# sch.net
KiCad netlist of a schematic drawn in EAGLE
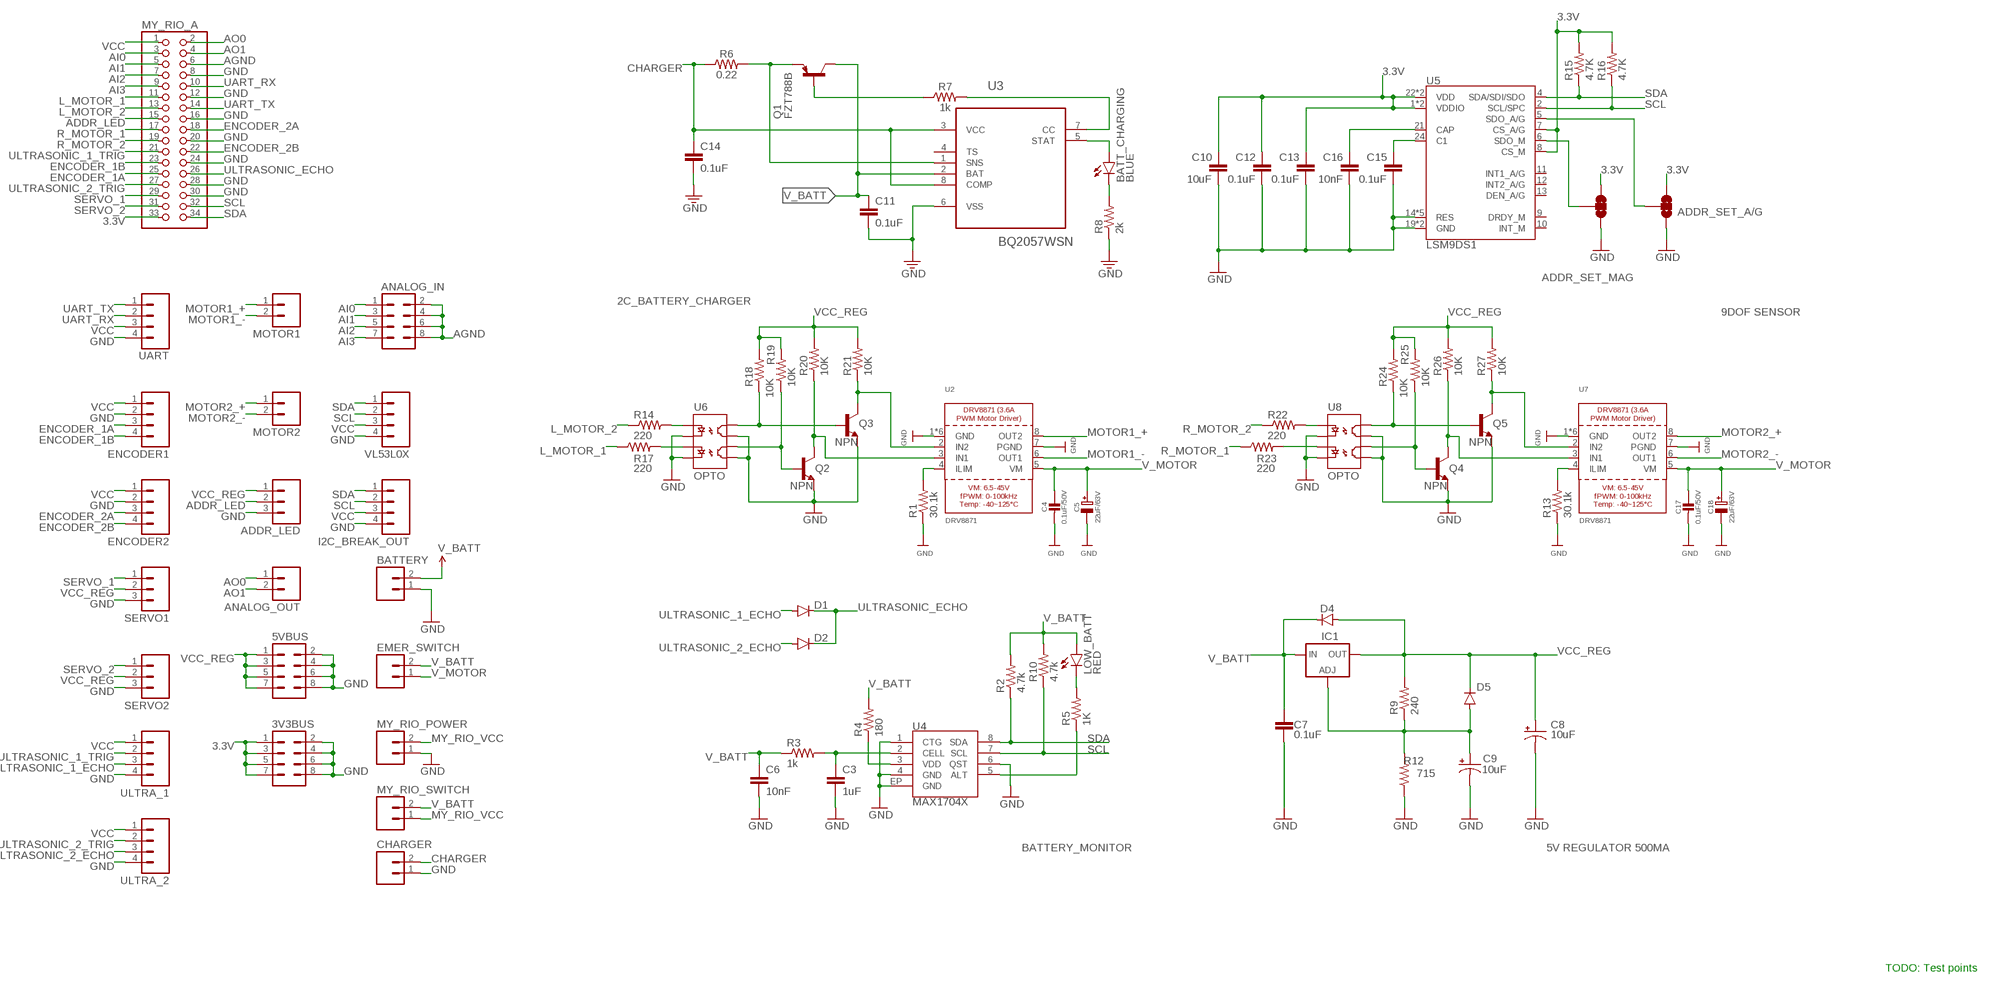
[diagram p0: schematic, sheet 1]

(export (version "E")
  (design (tool "Eeschema 10.0.6"))
  (components
    (comp (ref "3V3BUS")
      (value "M04X2")
      (footprint "eagle-import:2X4")
      (libsource (lib "eagle-import") (part "M04X2"))
    )
    (comp (ref "5VBUS")
      (value "M04X2")
      (footprint "eagle-import:2X4")
      (libsource (lib "eagle-import") (part "M04X2"))
    )
    (comp (ref "ADDR_LED")
      (value "M03POLAR")
      (footprint "eagle-import:MOLEX-1X3")
      (libsource (lib "eagle-import") (part "M03POLAR"))
    )
    (comp (ref "ADDR_SET_A/G")
      (value "JUMPER-PAD-3-2OF3_NC_BY_TRACE_SMALL")
      (footprint "eagle-import:PAD-JUMPER-3-2OF3_NC_BY_TRACE_YES_SILK_FULL_BOX")
      (libsource (lib "eagle-import") (part "JUMPER-PAD-3-2OF3_NC_BY_TRACE_SMALL"))
    )
    (comp (ref "ADDR_SET_MAG")
      (value "JUMPER-PAD-3-2OF3_NC_BY_TRACE_SMALL")
      (footprint "eagle-import:PAD-JUMPER-3-2OF3_NC_BY_TRACE_YES_SILK_FULL_BOX")
      (libsource (lib "eagle-import") (part "JUMPER-PAD-3-2OF3_NC_BY_TRACE_SMALL"))
    )
    (comp (ref "ANALOG_IN")
      (value "M04X2")
      (footprint "eagle-import:2X4")
      (libsource (lib "eagle-import") (part "M04X2"))
    )
    (comp (ref "ANALOG_OUT")
      (value "M021X02_NO_SILK")
      (footprint "eagle-import:1X02_NO_SILK@1")
      (libsource (lib "eagle-import") (part "M021X02_NO_SILK"))
    )
    (comp (ref "BATTERY")
      (value "CONN_02")
      (footprint "eagle-import:1X02")
      (libsource (lib "eagle-import") (part "CONN_02"))
    )
    (comp (ref "BATT_CHARGING")
      (value "BLUE")
      (footprint "eagle-import:LED-0603")
      (libsource (lib "eagle-import") (part "LED-BLUE0603"))
    )
    (comp (ref "C3")
      (value "1uF")
      (footprint "eagle-import:0402-CAP")
      (libsource (lib "eagle-import") (part "CAP0402-CAP"))
    )
    (comp (ref "C4")
      (value "0.1uF/50V")
      (footprint "eagle-import:0805-NO")
      (libsource (lib "eagle-import") (part "CAP_CERAMIC0805-NOOUTLINE"))
    )
    (comp (ref "C5")
      (value "22uF/63V")
      (footprint "eagle-import:PANASONIC_D")
      (libsource (lib "eagle-import") (part "CAP_ELECTROLYTICPANASONIC_D"))
    )
    (comp (ref "C6")
      (value "10nF")
      (footprint "eagle-import:0402-CAP")
      (libsource (lib "eagle-import") (part "CAP0402-CAP"))
    )
    (comp (ref "C7")
      (value "0.1uF")
      (footprint "eagle-import:0603-CAP")
      (libsource (lib "eagle-import") (part "0.1UF-25V(+80/-20%)(0603)"))
    )
    (comp (ref "C8")
      (value "10uF")
      (footprint "eagle-import:EIA3216")
      (libsource (lib "eagle-import") (part "10UF-16V-10%(TANT)"))
    )
    (comp (ref "C9")
      (value "10uF")
      (footprint "eagle-import:EIA3216")
      (libsource (lib "eagle-import") (part "10UF-16V-10%(TANT)"))
    )
    (comp (ref "C10")
      (value "10uF")
      (footprint "eagle-import:0603-CAP")
      (libsource (lib "eagle-import") (part "10UF-6.3V-20%(0603)"))
    )
    (comp (ref "C11")
      (value "0.1uF")
      (footprint "eagle-import:0603")
      (libsource (lib "eagle-import") (part "0.1UF-0603-25V-(+80/-20%)"))
    )
    (comp (ref "C12")
      (value "0.1uF")
      (footprint "eagle-import:0603-CAP")
      (libsource (lib "eagle-import") (part "0.1UF-25V(+80/-20%)(0603)"))
    )
    (comp (ref "C13")
      (value "0.1uF")
      (footprint "eagle-import:0603-CAP")
      (libsource (lib "eagle-import") (part "0.1UF-25V(+80/-20%)(0603)"))
    )
    (comp (ref "C14")
      (value "0.1uF")
      (footprint "eagle-import:0603")
      (libsource (lib "eagle-import") (part "0.1UF-0603-25V-(+80/-20%)"))
    )
    (comp (ref "C15")
      (value "0.1uF")
      (footprint "eagle-import:0603-CAP")
      (libsource (lib "eagle-import") (part "0.1UF-25V(+80/-20%)(0603)"))
    )
    (comp (ref "C16")
      (value "10nF")
      (footprint "eagle-import:0603-CAP")
      (libsource (lib "eagle-import") (part "10NF/10000PF-50V-10%(0603)"))
    )
    (comp (ref "C17")
      (value "0.1uF/50V")
      (footprint "eagle-import:0805-NO")
      (libsource (lib "eagle-import") (part "CAP_CERAMIC0805-NOOUTLINE"))
    )
    (comp (ref "C18")
      (value "22uF/63V")
      (footprint "eagle-import:PANASONIC_D")
      (libsource (lib "eagle-import") (part "CAP_ELECTROLYTICPANASONIC_D"))
    )
    (comp (ref "CHARGER")
      (value "CONN_02")
      (footprint "eagle-import:1X02")
      (libsource (lib "eagle-import") (part "CONN_02"))
    )
    (comp (ref "D1")
      (value "DIODESOD123")
      (footprint "eagle-import:SOD-123")
      (libsource (lib "eagle-import") (part "DIODESOD123"))
    )
    (comp (ref "D2")
      (value "DIODESOD123")
      (footprint "eagle-import:SOD-123")
      (libsource (lib "eagle-import") (part "DIODESOD123"))
    )
    (comp (ref "D4")
      (value "1N4002")
      (footprint "eagle-import:SOD-123")
      (libsource (lib "eagle-import") (part "DIODESOD123"))
    )
    (comp (ref "D5")
      (value "1N4002")
      (footprint "eagle-import:SOD-123")
      (libsource (lib "eagle-import") (part "DIODESOD123"))
    )
    (comp (ref "EMER_SWITCH")
      (value "CONN_02")
      (footprint "eagle-import:1X02")
      (libsource (lib "eagle-import") (part "CONN_02"))
    )
    (comp (ref "ENCODER1")
      (value "M041X04_NO_SILK")
      (footprint "eagle-import:1X04_NO_SILK")
      (libsource (lib "eagle-import") (part "M041X04_NO_SILK"))
    )
    (comp (ref "ENCODER2")
      (value "M041X04_NO_SILK")
      (footprint "eagle-import:1X04_NO_SILK")
      (libsource (lib "eagle-import") (part "M041X04_NO_SILK"))
    )
    (comp (ref "I2C_BREAK_OUT")
      (value "M041X04_NO_SILK")
      (footprint "eagle-import:1X04_NO_SILK")
      (libsource (lib "eagle-import") (part "M041X04_NO_SILK"))
    )
    (comp (ref "IC1")
      (value "LM317MBSTT3")
      (footprint "eagle-import:SOT223")
      (fields (field (name "PARTNUMBER") "LM317M"))
      (libsource (lib "eagle-import") (part "LM317?MBSTT3"))
    )
    (comp (ref "LOW_BATT")
      (value "RED")
      (footprint "eagle-import:LED-0603")
      (libsource (lib "eagle-import") (part "LED-RED0603"))
    )
    (comp (ref "MOTOR1")
      (value "M02PTH")
      (footprint "eagle-import:1X02@1")
      (libsource (lib "eagle-import") (part "M02PTH"))
    )
    (comp (ref "MOTOR2")
      (value "M02PTH")
      (footprint "eagle-import:1X02@1")
      (libsource (lib "eagle-import") (part "M02PTH"))
    )
    (comp (ref "MY_RIO_A")
      (value "PINHD-2X17")
      (footprint "eagle-import:2X17")
      (libsource (lib "eagle-import") (part "PINHD-2X17"))
    )
    (comp (ref "MY_RIO_POWER")
      (value "CONN_02")
      (footprint "eagle-import:1X02")
      (libsource (lib "eagle-import") (part "CONN_02"))
    )
    (comp (ref "MY_RIO_SWITCH")
      (value "CONN_02")
      (footprint "eagle-import:1X02")
      (libsource (lib "eagle-import") (part "CONN_02"))
    )
    (comp (ref "Q1")
      (value "FZT788B")
      (footprint "eagle-import:SOT230P700X180-4N")
      (libsource (lib "eagle-import") (part "FZT788B"))
    )
    (comp (ref "Q2")
      (value "NPN")
      (footprint "eagle-import:SOT23-3")
      (libsource (lib "eagle-import") (part "TRANSISTOR_NPNSOT23-3"))
    )
    (comp (ref "Q3")
      (value "NPN")
      (footprint "eagle-import:SOT23-3")
      (libsource (lib "eagle-import") (part "TRANSISTOR_NPNSOT23-3"))
    )
    (comp (ref "Q4")
      (value "NPN")
      (footprint "eagle-import:SOT23-3")
      (libsource (lib "eagle-import") (part "TRANSISTOR_NPNSOT23-3"))
    )
    (comp (ref "Q5")
      (value "NPN")
      (footprint "eagle-import:SOT23-3")
      (libsource (lib "eagle-import") (part "TRANSISTOR_NPNSOT23-3"))
    )
    (comp (ref "R1")
      (value "30.1k")
      (footprint "eagle-import:0603-RES")
      (libsource (lib "eagle-import") (part "30.1KOHM1/10W1%(0603)"))
    )
    (comp (ref "R2")
      (value "4.7k")
      (footprint "eagle-import:0402-RES")
      (libsource (lib "eagle-import") (part "RESISTOR0402-RES"))
    )
    (comp (ref "R3")
      (value "1k")
      (footprint "eagle-import:0402-RES")
      (libsource (lib "eagle-import") (part "RESISTOR0402-RES"))
    )
    (comp (ref "R4")
      (value "180")
      (footprint "eagle-import:0402-RES")
      (libsource (lib "eagle-import") (part "RESISTOR0402-RES"))
    )
    (comp (ref "R5")
      (value "1K")
      (footprint "eagle-import:0603-RES")
      (libsource (lib "eagle-import") (part "1KOHM-1/10W-1%(0603)"))
    )
    (comp (ref "R6")
      (value "0.22")
      (footprint "eagle-import:0805@1")
      (libsource (lib "eagle-import") (part "0.22OHM-0805-1/4W-1%"))
    )
    (comp (ref "R7")
      (value "1k")
      (footprint "eagle-import:0603")
      (libsource (lib "eagle-import") (part "1KOHM-0603-1/10W-1%"))
    )
    (comp (ref "R8")
      (value "2k")
      (footprint "eagle-import:0603-RES")
      (libsource (lib "eagle-import") (part "RESISTOR0603"))
    )
    (comp (ref "R9")
      (value "240")
      (footprint "eagle-import:0603-RES")
      (libsource (lib "eagle-import") (part "240OHM1/10W1%(0603)"))
    )
    (comp (ref "R10")
      (value "4.7k")
      (footprint "eagle-import:0402-RES")
      (libsource (lib "eagle-import") (part "RESISTOR0402-RES"))
    )
    (comp (ref "R12")
      (value "715")
      (footprint "eagle-import:0603-RES")
      (libsource (lib "eagle-import") (part "715OHM1/10W1%(0603)"))
    )
    (comp (ref "R13")
      (value "30.1k")
      (footprint "eagle-import:0603-RES")
      (libsource (lib "eagle-import") (part "30.1KOHM1/10W1%(0603)"))
    )
    (comp (ref "R14")
      (value "220")
      (footprint "eagle-import:0603-RES")
      (libsource (lib "eagle-import") (part "220OHM-1/10W-1%(0603)"))
    )
    (comp (ref "R15")
      (value "4.7K")
      (footprint "eagle-import:0603-RES")
      (libsource (lib "eagle-import") (part "4.7KOHM-1/10W-1%(0603)"))
    )
    (comp (ref "R16")
      (value "4.7K")
      (footprint "eagle-import:0603-RES")
      (libsource (lib "eagle-import") (part "4.7KOHM-1/10W-1%(0603)"))
    )
    (comp (ref "R17")
      (value "220")
      (footprint "eagle-import:0603-RES")
      (libsource (lib "eagle-import") (part "220OHM-1/10W-1%(0603)"))
    )
    (comp (ref "R18")
      (value "10K")
      (footprint "eagle-import:0603-RES")
      (libsource (lib "eagle-import") (part "10KOHM-1/10W-1%(0603)0603"))
    )
    (comp (ref "R19")
      (value "10K")
      (footprint "eagle-import:0603-RES")
      (libsource (lib "eagle-import") (part "10KOHM-1/10W-1%(0603)0603"))
    )
    (comp (ref "R20")
      (value "10K")
      (footprint "eagle-import:0603-RES")
      (libsource (lib "eagle-import") (part "10KOHM-1/10W-1%(0603)0603"))
    )
    (comp (ref "R21")
      (value "10K")
      (footprint "eagle-import:0603-RES")
      (libsource (lib "eagle-import") (part "10KOHM-1/10W-1%(0603)0603"))
    )
    (comp (ref "R22")
      (value "220")
      (footprint "eagle-import:0603-RES")
      (libsource (lib "eagle-import") (part "220OHM-1/10W-1%(0603)"))
    )
    (comp (ref "R23")
      (value "220")
      (footprint "eagle-import:0603-RES")
      (libsource (lib "eagle-import") (part "220OHM-1/10W-1%(0603)"))
    )
    (comp (ref "R24")
      (value "10K")
      (footprint "eagle-import:0603-RES")
      (libsource (lib "eagle-import") (part "10KOHM-1/10W-1%(0603)0603"))
    )
    (comp (ref "R25")
      (value "10K")
      (footprint "eagle-import:0603-RES")
      (libsource (lib "eagle-import") (part "10KOHM-1/10W-1%(0603)0603"))
    )
    (comp (ref "R26")
      (value "10K")
      (footprint "eagle-import:0603-RES")
      (libsource (lib "eagle-import") (part "10KOHM-1/10W-1%(0603)0603"))
    )
    (comp (ref "R27")
      (value "10K")
      (footprint "eagle-import:0603-RES")
      (libsource (lib "eagle-import") (part "10KOHM-1/10W-1%(0603)0603"))
    )
    (comp (ref "SERVO1")
      (value "M03POLAR")
      (footprint "eagle-import:MOLEX-1X3")
      (libsource (lib "eagle-import") (part "M03POLAR"))
    )
    (comp (ref "SERVO2")
      (value "M03POLAR")
      (footprint "eagle-import:MOLEX-1X3")
      (libsource (lib "eagle-import") (part "M03POLAR"))
    )
    (comp (ref "U2")
      (value "DRV8871")
      (footprint "eagle-import:HSOP8")
      (libsource (lib "eagle-import") (part "DRV8871"))
    )
    (comp (ref "U3")
      (value "BQ2057WSN")
      (footprint "eagle-import:SOIC127P600X175-8N")
      (fields (field (name "MF") "Texas Instruments"))
      (libsource (lib "eagle-import") (part "BQ2057WSN"))
    )
    (comp (ref "U4")
      (value "MAX1704X")
      (footprint "eagle-import:TDFN-8")
      (libsource (lib "eagle-import") (part "MAX1704X"))
    )
    (comp (ref "U5")
      (value "LSM9DS1")
      (footprint "eagle-import:LGA24-8X4")
      (libsource (lib "eagle-import") (part "LSM9DS1"))
    )
    (comp (ref "U6")
      (value "OPTO")
      (footprint "eagle-import:SO08-2")
      (libsource (lib "eagle-import") (part "OPTOISOLATOR-2SOIC8"))
    )
    (comp (ref "U7")
      (value "DRV8871")
      (footprint "eagle-import:HSOP8")
      (libsource (lib "eagle-import") (part "DRV8871"))
    )
    (comp (ref "U8")
      (value "OPTO")
      (footprint "eagle-import:SO08-2")
      (libsource (lib "eagle-import") (part "OPTOISOLATOR-2SOIC8"))
    )
    (comp (ref "UART")
      (value "M04NO_SILK_ALL_ROUND")
      (footprint "eagle-import:1X04_NO_SILK_ALL_ROUND")
      (libsource (lib "eagle-import") (part "M04NO_SILK_ALL_ROUND"))
    )
    (comp (ref "ULTRA_1")
      (value "M041X04_NO_SILK")
      (footprint "eagle-import:1X04_NO_SILK")
      (libsource (lib "eagle-import") (part "M041X04_NO_SILK"))
    )
    (comp (ref "ULTRA_2")
      (value "M041X04_NO_SILK")
      (footprint "eagle-import:1X04_NO_SILK")
      (libsource (lib "eagle-import") (part "M041X04_NO_SILK"))
    )
    (comp (ref "VL53L0X")
      (value "M041X04_NO_SILK")
      (footprint "eagle-import:1X04_NO_SILK")
      (libsource (lib "eagle-import") (part "M041X04_NO_SILK"))
    )
  )
  (nets
    (net (code "1") (name "/3.3V") (class "Default")
      (node (ref "3V3BUS") (pin "1") (pinfunction "1_1") (pintype "passive"))
      (node (ref "3V3BUS") (pin "3") (pinfunction "3_3") (pintype "passive"))
      (node (ref "3V3BUS") (pin "5") (pinfunction "5_5") (pintype "passive"))
      (node (ref "3V3BUS") (pin "7") (pinfunction "7_7") (pintype "passive"))
      (node (ref "ADDR_SET_A/G") (pin "3") (pinfunction "3_3") (pintype "passive"))
      (node (ref "ADDR_SET_MAG") (pin "3") (pinfunction "3_3") (pintype "passive"))
      (node (ref "C10") (pin "1") (pinfunction "1_1") (pintype "passive"))
      (node (ref "C12") (pin "1") (pinfunction "1_1") (pintype "passive"))
      (node (ref "C13") (pin "1") (pinfunction "1_1") (pintype "passive"))
      (node (ref "MY_RIO_A") (pin "33") (pinfunction "33_33") (pintype "passive"))
      (node (ref "R15") (pin "2") (pinfunction "2_2") (pintype "passive"))
      (node (ref "R16") (pin "2") (pinfunction "2_2") (pintype "passive"))
      (node (ref "U5") (pin "1") (pinfunction "VDDIO_1") (pintype "bidirectional"))
      (node (ref "U5") (pin "22") (pinfunction "VDD_22") (pintype "bidirectional"))
      (node (ref "U5") (pin "23") (pinfunction "VDD_23") (pintype "bidirectional"))
      (node (ref "U5") (pin "3") (pinfunction "VDDIO_3") (pintype "bidirectional"))
      (node (ref "U5") (pin "7") (pinfunction "CS_A/G_7") (pintype "bidirectional"))
      (node (ref "U5") (pin "8") (pinfunction "CS_M_8") (pintype "bidirectional"))
    )
    (net (code "2") (name "/ADDR_LED") (class "Default")
      (node (ref "ADDR_LED") (pin "2") (pinfunction "2_2") (pintype "passive"))
      (node (ref "MY_RIO_A") (pin "15") (pinfunction "15_15") (pintype "passive"))
    )
    (net (code "3") (name "/AGND") (class "Default")
      (node (ref "ANALOG_IN") (pin "2") (pinfunction "2_2") (pintype "passive"))
      (node (ref "ANALOG_IN") (pin "4") (pinfunction "4_4") (pintype "passive"))
      (node (ref "ANALOG_IN") (pin "6") (pinfunction "6_6") (pintype "passive"))
      (node (ref "ANALOG_IN") (pin "8") (pinfunction "8_8") (pintype "passive"))
      (node (ref "MY_RIO_A") (pin "6") (pinfunction "6_6") (pintype "passive"))
    )
    (net (code "4") (name "/AI0") (class "Default")
      (node (ref "ANALOG_IN") (pin "1") (pinfunction "1_1") (pintype "passive"))
      (node (ref "MY_RIO_A") (pin "3") (pinfunction "3_3") (pintype "passive"))
    )
    (net (code "5") (name "/AI1") (class "Default")
      (node (ref "ANALOG_IN") (pin "3") (pinfunction "3_3") (pintype "passive"))
      (node (ref "MY_RIO_A") (pin "5") (pinfunction "5_5") (pintype "passive"))
    )
    (net (code "6") (name "/AI2") (class "Default")
      (node (ref "ANALOG_IN") (pin "5") (pinfunction "5_5") (pintype "passive"))
      (node (ref "MY_RIO_A") (pin "7") (pinfunction "7_7") (pintype "passive"))
    )
    (net (code "7") (name "/AI3") (class "Default")
      (node (ref "ANALOG_IN") (pin "7") (pinfunction "7_7") (pintype "passive"))
      (node (ref "MY_RIO_A") (pin "9") (pinfunction "9_9") (pintype "passive"))
    )
    (net (code "8") (name "/AO0") (class "Default")
      (node (ref "ANALOG_OUT") (pin "1") (pinfunction "1_1") (pintype "passive"))
      (node (ref "MY_RIO_A") (pin "2") (pinfunction "2_2") (pintype "passive"))
    )
    (net (code "9") (name "/AO1") (class "Default")
      (node (ref "ANALOG_OUT") (pin "2") (pinfunction "2_2") (pintype "passive"))
      (node (ref "MY_RIO_A") (pin "4") (pinfunction "4_4") (pintype "passive"))
    )
    (net (code "10") (name "/CHARGER") (class "Default")
      (node (ref "C14") (pin "1") (pinfunction "1_1") (pintype "passive"))
      (node (ref "CHARGER") (pin "2") (pinfunction "2_2") (pintype "passive"))
      (node (ref "R6") (pin "1") (pinfunction "1_1") (pintype "passive"))
      (node (ref "U3") (pin "3") (pinfunction "VCC_3") (pintype "power_in"))
      (node (ref "U3") (pin "8") (pinfunction "COMP_8") (pintype "input"))
    )
    (net (code "11") (name "/ENCODER_1A") (class "Default")
      (node (ref "ENCODER1") (pin "3") (pinfunction "3_3") (pintype "passive"))
      (node (ref "MY_RIO_A") (pin "25") (pinfunction "25_25") (pintype "passive"))
    )
    (net (code "12") (name "/ENCODER_1B") (class "Default")
      (node (ref "ENCODER1") (pin "4") (pinfunction "4_4") (pintype "passive"))
      (node (ref "MY_RIO_A") (pin "23") (pinfunction "23_23") (pintype "passive"))
    )
    (net (code "13") (name "/ENCODER_2A") (class "Default")
      (node (ref "ENCODER2") (pin "3") (pinfunction "3_3") (pintype "passive"))
      (node (ref "MY_RIO_A") (pin "18") (pinfunction "18_18") (pintype "passive"))
    )
    (net (code "14") (name "/ENCODER_2B") (class "Default")
      (node (ref "ENCODER2") (pin "4") (pinfunction "4_4") (pintype "passive"))
      (node (ref "MY_RIO_A") (pin "22") (pinfunction "22_22") (pintype "passive"))
    )
    (net (code "15") (name "/L_MOTOR_1") (class "Default")
      (node (ref "MY_RIO_A") (pin "11") (pinfunction "11_11") (pintype "passive"))
      (node (ref "R17") (pin "1") (pinfunction "1_1") (pintype "passive"))
    )
    (net (code "16") (name "/L_MOTOR_2") (class "Default")
      (node (ref "MY_RIO_A") (pin "13") (pinfunction "13_13") (pintype "passive"))
      (node (ref "R14") (pin "1") (pinfunction "1_1") (pintype "passive"))
    )
    (net (code "17") (name "/MOTOR1_+") (class "Default")
      (node (ref "MOTOR1") (pin "1") (pinfunction "1_1") (pintype "passive"))
      (node (ref "U2") (pin "8") (pinfunction "OUT2_8") (pintype "output"))
    )
    (net (code "18") (name "/MOTOR1_-") (class "Default")
      (node (ref "MOTOR1") (pin "2") (pinfunction "2_2") (pintype "passive"))
      (node (ref "U2") (pin "6") (pinfunction "OUT1_6") (pintype "output"))
    )
    (net (code "19") (name "/MOTOR2_+") (class "Default")
      (node (ref "MOTOR2") (pin "1") (pinfunction "1_1") (pintype "passive"))
      (node (ref "U7") (pin "8") (pinfunction "OUT2_8") (pintype "output"))
    )
    (net (code "20") (name "/MOTOR2_-") (class "Default")
      (node (ref "MOTOR2") (pin "2") (pinfunction "2_2") (pintype "passive"))
      (node (ref "U7") (pin "6") (pinfunction "OUT1_6") (pintype "output"))
    )
    (net (code "21") (name "/MY_RIO_VCC") (class "Default")
      (node (ref "MY_RIO_POWER") (pin "2") (pinfunction "2_2") (pintype "passive"))
      (node (ref "MY_RIO_SWITCH") (pin "1") (pinfunction "1_1") (pintype "passive"))
    )
    (net (code "22") (name "/R_MOTOR_1") (class "Default")
      (node (ref "MY_RIO_A") (pin "17") (pinfunction "17_17") (pintype "passive"))
      (node (ref "R23") (pin "1") (pinfunction "1_1") (pintype "passive"))
    )
    (net (code "23") (name "/R_MOTOR_2") (class "Default")
      (node (ref "MY_RIO_A") (pin "19") (pinfunction "19_19") (pintype "passive"))
      (node (ref "R22") (pin "1") (pinfunction "1_1") (pintype "passive"))
    )
    (net (code "24") (name "/SCL") (class "Default")
      (node (ref "I2C_BREAK_OUT") (pin "2") (pinfunction "2_2") (pintype "passive"))
      (node (ref "MY_RIO_A") (pin "32") (pinfunction "32_32") (pintype "passive"))
      (node (ref "R10") (pin "1") (pinfunction "1_1") (pintype "passive"))
      (node (ref "R16") (pin "1") (pinfunction "1_1") (pintype "passive"))
      (node (ref "U4") (pin "7") (pinfunction "SCL_7") (pintype "bidirectional"))
      (node (ref "U5") (pin "2") (pinfunction "SCL/SPC_2") (pintype "bidirectional"))
      (node (ref "VL53L0X") (pin "2") (pinfunction "2_2") (pintype "passive"))
    )
    (net (code "25") (name "/SDA") (class "Default")
      (node (ref "I2C_BREAK_OUT") (pin "1") (pinfunction "1_1") (pintype "passive"))
      (node (ref "MY_RIO_A") (pin "34") (pinfunction "34_34") (pintype "passive"))
      (node (ref "R15") (pin "1") (pinfunction "1_1") (pintype "passive"))
      (node (ref "R2") (pin "1") (pinfunction "1_1") (pintype "passive"))
      (node (ref "U4") (pin "8") (pinfunction "SDA_8") (pintype "bidirectional"))
      (node (ref "U5") (pin "4") (pinfunction "SDA/SDI/SDO_4") (pintype "bidirectional"))
      (node (ref "VL53L0X") (pin "1") (pinfunction "1_1") (pintype "passive"))
    )
    (net (code "26") (name "/SERVO_1") (class "Default")
      (node (ref "MY_RIO_A") (pin "29") (pinfunction "29_29") (pintype "passive"))
      (node (ref "SERVO1") (pin "1") (pinfunction "1_1") (pintype "passive"))
    )
    (net (code "27") (name "/SERVO_2") (class "Default")
      (node (ref "MY_RIO_A") (pin "31") (pinfunction "31_31") (pintype "passive"))
      (node (ref "SERVO2") (pin "1") (pinfunction "1_1") (pintype "passive"))
    )
    (net (code "28") (name "/UART_RX") (class "Default")
      (node (ref "MY_RIO_A") (pin "10") (pinfunction "10_10") (pintype "passive"))
      (node (ref "UART") (pin "2") (pinfunction "2_2") (pintype "passive"))
    )
    (net (code "29") (name "/UART_TX") (class "Default")
      (node (ref "MY_RIO_A") (pin "14") (pinfunction "14_14") (pintype "passive"))
      (node (ref "UART") (pin "1") (pinfunction "1_1") (pintype "passive"))
    )
    (net (code "30") (name "/ULTRASONIC_1_ECHO") (class "Default")
      (node (ref "D1") (pin "A") (pinfunction "A_A") (pintype "passive"))
      (node (ref "ULTRA_1") (pin "3") (pinfunction "3_3") (pintype "passive"))
    )
    (net (code "31") (name "/ULTRASONIC_1_TRIG") (class "Default")
      (node (ref "MY_RIO_A") (pin "21") (pinfunction "21_21") (pintype "passive"))
      (node (ref "ULTRA_1") (pin "2") (pinfunction "2_2") (pintype "passive"))
    )
    (net (code "32") (name "/ULTRASONIC_2_ECHO") (class "Default")
      (node (ref "D2") (pin "A") (pinfunction "A_A") (pintype "passive"))
      (node (ref "ULTRA_2") (pin "3") (pinfunction "3_3") (pintype "passive"))
    )
    (net (code "33") (name "/ULTRASONIC_2_TRIG") (class "Default")
      (node (ref "MY_RIO_A") (pin "27") (pinfunction "27_27") (pintype "passive"))
      (node (ref "ULTRA_2") (pin "2") (pinfunction "2_2") (pintype "passive"))
    )
    (net (code "34") (name "/ULTRASONIC_ECHO") (class "Default")
      (node (ref "D1") (pin "C") (pinfunction "C_C") (pintype "passive"))
      (node (ref "D2") (pin "C") (pinfunction "C_C") (pintype "passive"))
      (node (ref "MY_RIO_A") (pin "26") (pinfunction "26_26") (pintype "passive"))
    )
    (net (code "35") (name "/VCC") (class "Default")
      (node (ref "ENCODER1") (pin "1") (pinfunction "1_1") (pintype "passive"))
      (node (ref "ENCODER2") (pin "1") (pinfunction "1_1") (pintype "passive"))
      (node (ref "I2C_BREAK_OUT") (pin "3") (pinfunction "3_3") (pintype "passive"))
      (node (ref "MY_RIO_A") (pin "1") (pinfunction "1_1") (pintype "passive"))
      (node (ref "UART") (pin "3") (pinfunction "3_3") (pintype "passive"))
      (node (ref "ULTRA_1") (pin "1") (pinfunction "1_1") (pintype "passive"))
      (node (ref "ULTRA_2") (pin "1") (pinfunction "1_1") (pintype "passive"))
      (node (ref "VL53L0X") (pin "3") (pinfunction "3_3") (pintype "passive"))
    )
    (net (code "36") (name "/VCC_REG") (class "Default")
      (node (ref "5VBUS") (pin "1") (pinfunction "1_1") (pintype "passive"))
      (node (ref "5VBUS") (pin "3") (pinfunction "3_3") (pintype "passive"))
      (node (ref "5VBUS") (pin "5") (pinfunction "5_5") (pintype "passive"))
      (node (ref "5VBUS") (pin "7") (pinfunction "7_7") (pintype "passive"))
      (node (ref "ADDR_LED") (pin "1") (pinfunction "1_1") (pintype "passive"))
      (node (ref "C8") (pin "A") (pinfunction "+_A") (pintype "passive"))
      (node (ref "D4") (pin "A") (pinfunction "A_A") (pintype "passive"))
      (node (ref "D5") (pin "C") (pinfunction "C_C") (pintype "passive"))
      (node (ref "IC1") (pin "4") (pinfunction "OUT_4") (pintype "passive"))
      (node (ref "R18") (pin "2") (pinfunction "2_2") (pintype "passive"))
      (node (ref "R19") (pin "2") (pinfunction "2_2") (pintype "passive"))
      (node (ref "R20") (pin "2") (pinfunction "2_2") (pintype "passive"))
      (node (ref "R21") (pin "2") (pinfunction "2_2") (pintype "passive"))
      (node (ref "R24") (pin "2") (pinfunction "2_2") (pintype "passive"))
      (node (ref "R25") (pin "2") (pinfunction "2_2") (pintype "passive"))
      (node (ref "R26") (pin "2") (pinfunction "2_2") (pintype "passive"))
      (node (ref "R27") (pin "2") (pinfunction "2_2") (pintype "passive"))
      (node (ref "R9") (pin "2") (pinfunction "2_2") (pintype "passive"))
      (node (ref "SERVO1") (pin "2") (pinfunction "2_2") (pintype "passive"))
      (node (ref "SERVO2") (pin "2") (pinfunction "2_2") (pintype "passive"))
    )
    (net (code "37") (name "/V_MOTOR") (class "Default")
      (node (ref "C17") (pin "1") (pinfunction "1_1") (pintype "passive"))
      (node (ref "C18") (pin "+") (pinfunction "+_+") (pintype "passive"))
      (node (ref "C4") (pin "1") (pinfunction "1_1") (pintype "passive"))
      (node (ref "C5") (pin "+") (pinfunction "+_+") (pintype "passive"))
      (node (ref "EMER_SWITCH") (pin "1") (pinfunction "1_1") (pintype "passive"))
      (node (ref "U2") (pin "5") (pinfunction "VM_5") (pintype "power_in"))
      (node (ref "U7") (pin "5") (pinfunction "VM_5") (pintype "power_in"))
    )
    (net (code "38") (name "GND") (class "Default")
      (node (ref "3V3BUS") (pin "2") (pinfunction "2_2") (pintype "passive"))
      (node (ref "3V3BUS") (pin "4") (pinfunction "4_4") (pintype "passive"))
      (node (ref "3V3BUS") (pin "6") (pinfunction "6_6") (pintype "passive"))
      (node (ref "3V3BUS") (pin "8") (pinfunction "8_8") (pintype "passive"))
      (node (ref "5VBUS") (pin "2") (pinfunction "2_2") (pintype "passive"))
      (node (ref "5VBUS") (pin "4") (pinfunction "4_4") (pintype "passive"))
      (node (ref "5VBUS") (pin "6") (pinfunction "6_6") (pintype "passive"))
      (node (ref "5VBUS") (pin "8") (pinfunction "8_8") (pintype "passive"))
      (node (ref "ADDR_LED") (pin "3") (pinfunction "3_3") (pintype "passive"))
      (node (ref "ADDR_SET_A/G") (pin "1") (pinfunction "1_1") (pintype "passive"))
      (node (ref "ADDR_SET_MAG") (pin "1") (pinfunction "1_1") (pintype "passive"))
      (node (ref "BATTERY") (pin "1") (pinfunction "1_1") (pintype "passive"))
      (node (ref "C10") (pin "2") (pinfunction "2_2") (pintype "passive"))
      (node (ref "C11") (pin "2") (pinfunction "2_2") (pintype "passive"))
      (node (ref "C12") (pin "2") (pinfunction "2_2") (pintype "passive"))
      (node (ref "C13") (pin "2") (pinfunction "2_2") (pintype "passive"))
      (node (ref "C14") (pin "2") (pinfunction "2_2") (pintype "passive"))
      (node (ref "C15") (pin "2") (pinfunction "2_2") (pintype "passive"))
      (node (ref "C16") (pin "2") (pinfunction "2_2") (pintype "passive"))
      (node (ref "C17") (pin "2") (pinfunction "2_2") (pintype "passive"))
      (node (ref "C18") (pin "-") (pinfunction "-_-") (pintype "passive"))
      (node (ref "C3") (pin "2") (pinfunction "2_2") (pintype "passive"))
      (node (ref "C4") (pin "2") (pinfunction "2_2") (pintype "passive"))
      (node (ref "C5") (pin "-") (pinfunction "-_-") (pintype "passive"))
      (node (ref "C6") (pin "2") (pinfunction "2_2") (pintype "passive"))
      (node (ref "C7") (pin "2") (pinfunction "2_2") (pintype "passive"))
      (node (ref "C8") (pin "C") (pinfunction "-_C") (pintype "passive"))
      (node (ref "C9") (pin "C") (pinfunction "-_C") (pintype "passive"))
      (node (ref "CHARGER") (pin "1") (pinfunction "1_1") (pintype "passive"))
      (node (ref "ENCODER1") (pin "2") (pinfunction "2_2") (pintype "passive"))
      (node (ref "ENCODER2") (pin "2") (pinfunction "2_2") (pintype "passive"))
      (node (ref "I2C_BREAK_OUT") (pin "4") (pinfunction "4_4") (pintype "passive"))
      (node (ref "MY_RIO_A") (pin "12") (pinfunction "12_12") (pintype "passive"))
      (node (ref "MY_RIO_A") (pin "16") (pinfunction "16_16") (pintype "passive"))
      (node (ref "MY_RIO_A") (pin "20") (pinfunction "20_20") (pintype "passive"))
      (node (ref "MY_RIO_A") (pin "24") (pinfunction "24_24") (pintype "passive"))
      (node (ref "MY_RIO_A") (pin "28") (pinfunction "28_28") (pintype "passive"))
      (node (ref "MY_RIO_A") (pin "30") (pinfunction "30_30") (pintype "passive"))
      (node (ref "MY_RIO_A") (pin "8") (pinfunction "8_8") (pintype "passive"))
      (node (ref "MY_RIO_POWER") (pin "1") (pinfunction "1_1") (pintype "passive"))
      (node (ref "Q2") (pin "2") (pinfunction "E_2") (pintype "passive"))
      (node (ref "Q3") (pin "2") (pinfunction "E_2") (pintype "passive"))
      (node (ref "Q4") (pin "2") (pinfunction "E_2") (pintype "passive"))
      (node (ref "Q5") (pin "2") (pinfunction "E_2") (pintype "passive"))
      (node (ref "R1") (pin "1") (pinfunction "1_1") (pintype "passive"))
      (node (ref "R12") (pin "1") (pinfunction "1_1") (pintype "passive"))
      (node (ref "R13") (pin "1") (pinfunction "1_1") (pintype "passive"))
      (node (ref "R8") (pin "1") (pinfunction "1_1") (pintype "passive"))
      (node (ref "SERVO1") (pin "3") (pinfunction "3_3") (pintype "passive"))
      (node (ref "SERVO2") (pin "3") (pinfunction "3_3") (pintype "passive"))
      (node (ref "U2") (pin "1") (pinfunction "GND_1") (pintype "power_in"))
      (node (ref "U2") (pin "7") (pinfunction "PGND_7") (pintype "power_in"))
      (node (ref "U2") (pin "GND") (pinfunction "GND_GND") (pintype "power_in"))
      (node (ref "U2") (pin "P$1") (pinfunction "GND_P$1") (pintype "power_in"))
      (node (ref "U2") (pin "P$2") (pinfunction "GND_P$2") (pintype "power_in"))
      (node (ref "U2") (pin "P$3") (pinfunction "GND_P$3") (pintype "power_in"))
      (node (ref "U2") (pin "P$4") (pinfunction "GND_P$4") (pintype "power_in"))
      (node (ref "U3") (pin "6") (pinfunction "VSS_6") (pintype "power_in"))
      (node (ref "U4") (pin "1") (pinfunction "CTG_1") (pintype "bidirectional"))
      (node (ref "U4") (pin "4") (pinfunction "GND_4") (pintype "bidirectional"))
      (node (ref "U4") (pin "6") (pinfunction "QST_6") (pintype "bidirectional"))
      (node (ref "U4") (pin "EP") (pinfunction "GND_EP") (pintype "bidirectional"))
      (node (ref "U5") (pin "14") (pinfunction "RES_14") (pintype "bidirectional"))
      (node (ref "U5") (pin "15") (pinfunction "RES_15") (pintype "bidirectional"))
      (node (ref "U5") (pin "16") (pinfunction "RES_16") (pintype "bidirectional"))
      (node (ref "U5") (pin "17") (pinfunction "RES_17") (pintype "bidirectional"))
      (node (ref "U5") (pin "18") (pinfunction "RES_18") (pintype "bidirectional"))
      (node (ref "U5") (pin "19") (pinfunction "GND_19") (pintype "bidirectional"))
      (node (ref "U5") (pin "20") (pinfunction "GND_20") (pintype "bidirectional"))
      (node (ref "U6") (pin "2") (pinfunction "C1_2") (pintype "bidirectional"))
      (node (ref "U6") (pin "4") (pinfunction "C2_4") (pintype "bidirectional"))
      (node (ref "U6") (pin "5") (pinfunction "EM2_5") (pintype "bidirectional"))
      (node (ref "U6") (pin "7") (pinfunction "EM1_7") (pintype "bidirectional"))
      (node (ref "U7") (pin "1") (pinfunction "GND_1") (pintype "power_in"))
      (node (ref "U7") (pin "7") (pinfunction "PGND_7") (pintype "power_in"))
      (node (ref "U7") (pin "GND") (pinfunction "GND_GND") (pintype "power_in"))
      (node (ref "U7") (pin "P$1") (pinfunction "GND_P$1") (pintype "power_in"))
      (node (ref "U7") (pin "P$2") (pinfunction "GND_P$2") (pintype "power_in"))
      (node (ref "U7") (pin "P$3") (pinfunction "GND_P$3") (pintype "power_in"))
      (node (ref "U7") (pin "P$4") (pinfunction "GND_P$4") (pintype "power_in"))
      (node (ref "U8") (pin "2") (pinfunction "C1_2") (pintype "bidirectional"))
      (node (ref "U8") (pin "4") (pinfunction "C2_4") (pintype "bidirectional"))
      (node (ref "U8") (pin "5") (pinfunction "EM2_5") (pintype "bidirectional"))
      (node (ref "U8") (pin "7") (pinfunction "EM1_7") (pintype "bidirectional"))
      (node (ref "UART") (pin "4") (pinfunction "4_4") (pintype "passive"))
      (node (ref "ULTRA_1") (pin "4") (pinfunction "4_4") (pintype "passive"))
      (node (ref "ULTRA_2") (pin "4") (pinfunction "4_4") (pintype "passive"))
      (node (ref "VL53L0X") (pin "4") (pinfunction "4_4") (pintype "passive"))
    )
    (net (code "39") (name "Net-(BATT_CHARGING-PadC)") (class "Default")
      (node (ref "BATT_CHARGING") (pin "C") (pinfunction "C_C") (pintype "passive"))
      (node (ref "R8") (pin "2") (pinfunction "2_2") (pintype "passive"))
    )
    (net (code "40") (name "Net-(C9-+)") (class "Default")
      (node (ref "C9") (pin "A") (pinfunction "+_A") (pintype "passive"))
      (node (ref "D5") (pin "A") (pinfunction "A_A") (pintype "passive"))
      (node (ref "IC1") (pin "1") (pinfunction "ADJ_1") (pintype "input"))
      (node (ref "R12") (pin "2") (pinfunction "2_2") (pintype "passive"))
      (node (ref "R9") (pin "1") (pinfunction "1_1") (pintype "passive"))
    )
    (net (code "41") (name "Net-(LOW_BATT-PadC)") (class "Default")
      (node (ref "LOW_BATT") (pin "C") (pinfunction "C_C") (pintype "passive"))
      (node (ref "R5") (pin "2") (pinfunction "2_2") (pintype "passive"))
    )
    (net (code "42") (name "Net-(Q1-B)") (class "Default")
      (node (ref "Q1") (pin "1") (pinfunction "B_1") (pintype "passive"))
      (node (ref "R7") (pin "1") (pinfunction "1_1") (pintype "passive"))
    )
    (net (code "43") (name "Net-(Q1-E)") (class "Default")
      (node (ref "Q1") (pin "3") (pinfunction "E_3") (pintype "passive"))
      (node (ref "R6") (pin "2") (pinfunction "2_2") (pintype "passive"))
      (node (ref "U3") (pin "1") (pinfunction "SNS_1") (pintype "input"))
    )
    (net (code "44") (name "Net-(Q2-B)") (class "Default")
      (node (ref "Q2") (pin "1") (pinfunction "B_1") (pintype "passive"))
      (node (ref "R19") (pin "1") (pinfunction "1_1") (pintype "passive"))
      (node (ref "U6") (pin "6") (pinfunction "CL2_6") (pintype "bidirectional"))
    )
    (net (code "45") (name "Net-(Q2-C)") (class "Default")
      (node (ref "Q2") (pin "3") (pinfunction "C_3") (pintype "passive"))
      (node (ref "R20") (pin "1") (pinfunction "1_1") (pintype "passive"))
      (node (ref "U2") (pin "3") (pinfunction "IN1_3") (pintype "input"))
    )
    (net (code "46") (name "Net-(Q3-B)") (class "Default")
      (node (ref "Q3") (pin "1") (pinfunction "B_1") (pintype "passive"))
      (node (ref "R18") (pin "1") (pinfunction "1_1") (pintype "passive"))
      (node (ref "U6") (pin "8") (pinfunction "CL1_8") (pintype "bidirectional"))
    )
    (net (code "47") (name "Net-(Q3-C)") (class "Default")
      (node (ref "Q3") (pin "3") (pinfunction "C_3") (pintype "passive"))
      (node (ref "R21") (pin "1") (pinfunction "1_1") (pintype "passive"))
      (node (ref "U2") (pin "2") (pinfunction "IN2_2") (pintype "input"))
    )
    (net (code "48") (name "Net-(Q4-B)") (class "Default")
      (node (ref "Q4") (pin "1") (pinfunction "B_1") (pintype "passive"))
      (node (ref "R25") (pin "1") (pinfunction "1_1") (pintype "passive"))
      (node (ref "U8") (pin "6") (pinfunction "CL2_6") (pintype "bidirectional"))
    )
    (net (code "49") (name "Net-(Q4-C)") (class "Default")
      (node (ref "Q4") (pin "3") (pinfunction "C_3") (pintype "passive"))
      (node (ref "R26") (pin "1") (pinfunction "1_1") (pintype "passive"))
      (node (ref "U7") (pin "3") (pinfunction "IN1_3") (pintype "input"))
    )
    (net (code "50") (name "Net-(Q5-B)") (class "Default")
      (node (ref "Q5") (pin "1") (pinfunction "B_1") (pintype "passive"))
      (node (ref "R24") (pin "1") (pinfunction "1_1") (pintype "passive"))
      (node (ref "U8") (pin "8") (pinfunction "CL1_8") (pintype "bidirectional"))
    )
    (net (code "51") (name "Net-(Q5-C)") (class "Default")
      (node (ref "Q5") (pin "3") (pinfunction "C_3") (pintype "passive"))
      (node (ref "R27") (pin "1") (pinfunction "1_1") (pintype "passive"))
      (node (ref "U7") (pin "2") (pinfunction "IN2_2") (pintype "input"))
    )
    (net (code "52") (name "Net-(U2-ILIM)") (class "Default")
      (node (ref "R1") (pin "2") (pinfunction "2_2") (pintype "passive"))
      (node (ref "U2") (pin "4") (pinfunction "ILIM_4") (pintype "input"))
    )
    (net (code "53") (name "Net-(U3-CC)") (class "Default")
      (node (ref "R7") (pin "2") (pinfunction "2_2") (pintype "passive"))
      (node (ref "U3") (pin "7") (pinfunction "CC_7") (pintype "output"))
    )
    (net (code "54") (name "Net-(U3-STAT)") (class "Default")
      (node (ref "BATT_CHARGING") (pin "A") (pinfunction "A_A") (pintype "passive"))
      (node (ref "U3") (pin "5") (pinfunction "STAT_5") (pintype "output"))
    )
    (net (code "55") (name "Net-(U4-ALT)") (class "Default")
      (node (ref "R5") (pin "1") (pinfunction "1_1") (pintype "passive"))
      (node (ref "U4") (pin "5") (pinfunction "ALT_5") (pintype "bidirectional"))
    )
    (net (code "56") (name "Net-(U4-CELL)") (class "Default")
      (node (ref "C3") (pin "1") (pinfunction "1_1") (pintype "passive"))
      (node (ref "R3") (pin "2") (pinfunction "2_2") (pintype "passive"))
      (node (ref "U4") (pin "2") (pinfunction "CELL_2") (pintype "bidirectional"))
    )
    (net (code "57") (name "Net-(U4-VDD)") (class "Default")
      (node (ref "R4") (pin "1") (pinfunction "1_1") (pintype "passive"))
      (node (ref "U4") (pin "3") (pinfunction "VDD_3") (pintype "bidirectional"))
    )
    (net (code "58") (name "Net-(U5-C1)") (class "Default")
      (node (ref "C15") (pin "1") (pinfunction "1_1") (pintype "passive"))
      (node (ref "U5") (pin "24") (pinfunction "C1_24") (pintype "bidirectional"))
    )
    (net (code "59") (name "Net-(U5-CAP)") (class "Default")
      (node (ref "C16") (pin "1") (pinfunction "1_1") (pintype "passive"))
      (node (ref "U5") (pin "21") (pinfunction "CAP_21") (pintype "bidirectional"))
    )
    (net (code "60") (name "Net-(U5-SDO_A{slash}G)") (class "Default")
      (node (ref "ADDR_SET_A/G") (pin "2") (pinfunction "2_2") (pintype "passive"))
      (node (ref "U5") (pin "5") (pinfunction "SDO_A/G_5") (pintype "bidirectional"))
    )
    (net (code "61") (name "Net-(U5-SDO_M)") (class "Default")
      (node (ref "ADDR_SET_MAG") (pin "2") (pinfunction "2_2") (pintype "passive"))
      (node (ref "U5") (pin "6") (pinfunction "SDO_M_6") (pintype "bidirectional"))
    )
    (net (code "62") (name "Net-(U6-A1)") (class "Default")
      (node (ref "R14") (pin "2") (pinfunction "2_2") (pintype "passive"))
      (node (ref "U6") (pin "1") (pinfunction "A1_1") (pintype "bidirectional"))
    )
    (net (code "63") (name "Net-(U6-A2)") (class "Default")
      (node (ref "R17") (pin "2") (pinfunction "2_2") (pintype "passive"))
      (node (ref "U6") (pin "3") (pinfunction "A2_3") (pintype "bidirectional"))
    )
    (net (code "64") (name "Net-(U7-ILIM)") (class "Default")
      (node (ref "R13") (pin "2") (pinfunction "2_2") (pintype "passive"))
      (node (ref "U7") (pin "4") (pinfunction "ILIM_4") (pintype "input"))
    )
    (net (code "65") (name "Net-(U8-A1)") (class "Default")
      (node (ref "R22") (pin "2") (pinfunction "2_2") (pintype "passive"))
      (node (ref "U8") (pin "1") (pinfunction "A1_1") (pintype "bidirectional"))
    )
    (net (code "66") (name "Net-(U8-A2)") (class "Default")
      (node (ref "R23") (pin "2") (pinfunction "2_2") (pintype "passive"))
      (node (ref "U8") (pin "3") (pinfunction "A2_3") (pintype "bidirectional"))
    )
    (net (code "67") (name "V_BATT") (class "Default")
      (node (ref "BATTERY") (pin "2") (pinfunction "2_2") (pintype "passive"))
      (node (ref "C11") (pin "1") (pinfunction "1_1") (pintype "passive"))
      (node (ref "C6") (pin "1") (pinfunction "1_1") (pintype "passive"))
      (node (ref "C7") (pin "1") (pinfunction "1_1") (pintype "passive"))
      (node (ref "D4") (pin "C") (pinfunction "C_C") (pintype "passive"))
      (node (ref "EMER_SWITCH") (pin "2") (pinfunction "2_2") (pintype "passive"))
      (node (ref "IC1") (pin "3") (pinfunction "IN_3") (pintype "input"))
      (node (ref "LOW_BATT") (pin "A") (pinfunction "A_A") (pintype "passive"))
      (node (ref "MY_RIO_SWITCH") (pin "2") (pinfunction "2_2") (pintype "passive"))
      (node (ref "Q1") (pin "2") (pinfunction "C_2") (pintype "passive"))
      (node (ref "Q1") (pin "4") (pinfunction "C_4") (pintype "passive"))
      (node (ref "R10") (pin "2") (pinfunction "2_2") (pintype "passive"))
      (node (ref "R2") (pin "2") (pinfunction "2_2") (pintype "passive"))
      (node (ref "R3") (pin "1") (pinfunction "1_1") (pintype "passive"))
      (node (ref "R4") (pin "2") (pinfunction "2_2") (pintype "passive"))
      (node (ref "U3") (pin "2") (pinfunction "BAT_2") (pintype "input"))
    )
    (net (code "68") (name "unconnected-(U3-TS-Pad4)") (class "Default")
      (node (ref "U3") (pin "4") (pinfunction "TS_4") (pintype "input"))
    )
    (net (code "69") (name "unconnected-(U5-DEN_A{slash}G-Pad13)") (class "Default")
      (node (ref "U5") (pin "13") (pinfunction "DEN_A/G_13") (pintype "bidirectional"))
    )
    (net (code "70") (name "unconnected-(U5-DRDY_M-Pad9)") (class "Default")
      (node (ref "U5") (pin "9") (pinfunction "DRDY_M_9") (pintype "bidirectional"))
    )
    (net (code "71") (name "unconnected-(U5-INT1_A{slash}G-Pad11)") (class "Default")
      (node (ref "U5") (pin "11") (pinfunction "INT1_A/G_11") (pintype "bidirectional"))
    )
    (net (code "72") (name "unconnected-(U5-INT2_A{slash}G-Pad12)") (class "Default")
      (node (ref "U5") (pin "12") (pinfunction "INT2_A/G_12") (pintype "bidirectional"))
    )
    (net (code "73") (name "unconnected-(U5-INT_M-Pad10)") (class "Default")
      (node (ref "U5") (pin "10") (pinfunction "INT_M_10") (pintype "bidirectional"))
    )
  )
)
